# DoorNode.net
KiCad netlist of a schematic drawn in Altium Designer
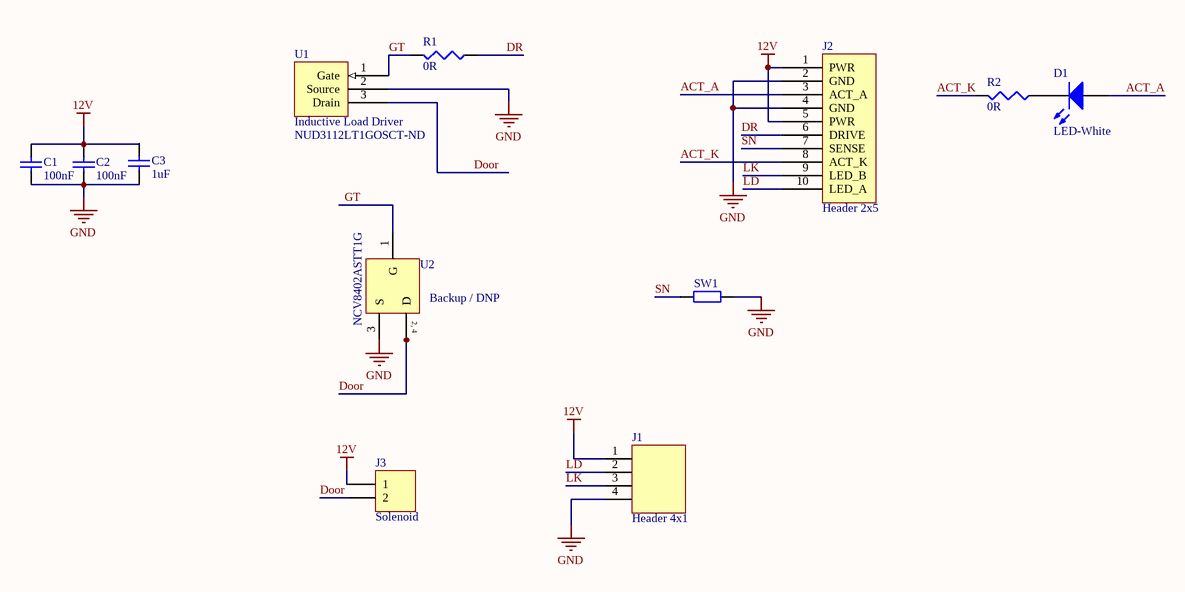
[diagram p0: DoorNode.SchDoc]

(export (version "E")
  (design (tool "Eeschema 10.0.6"))
  (components
    (comp (ref "C1")
      (value "100nF")
      (footprint "C1206")
      (description "Capacitor (Semiconductor SIM Model)")
      (fields (field (name "PUBLISHER") "Altium Limited"))
      (libsource (lib "ToolDoorController") (part "Cap 100nF"))
    )
    (comp (ref "C2")
      (value "100nF")
      (footprint "C1206")
      (description "Capacitor (Semiconductor SIM Model)")
      (fields (field (name "PUBLISHER") "Altium Limited"))
      (libsource (lib "ToolDoorController") (part "Cap 100nF"))
    )
    (comp (ref "C3")
      (value "1uF")
      (footprint "C1206")
      (description "Capacitor (Semiconductor SIM Model)")
      (fields (field (name "PUBLISHER") "Altium Limited"))
      (libsource (lib "ToolDoorController") (part "Cap 1uF"))
    )
    (comp (ref "D1")
      (value "LED-White")
      (footprint "STW8Q14")
      (description "White")
      (fields (field (name "PUBLISHER") "Altium Limited"))
      (libsource (lib "DoorNode") (part "LED-White"))
    )
    (comp (ref "J1")
      (value "Header 4x1")
      (footprint "4x1")
      (fields (field (name "PUBLISHER") "Altium Limited"))
      (libsource (lib "DoorNode") (part "Header 4x1"))
    )
    (comp (ref "J2")
      (value "Header 2x5")
      (footprint "2x5")
      (description "Header")
      (libsource (lib "DoorNode") (part "Header 2x5a"))
    )
    (comp (ref "J3")
      (value "Solenoid")
      (footprint "JST-XH")
      (description "Header, 2-Pin")
      (fields (field (name "PUBLISHER") "Altium Limited"))
      (libsource (lib "DoorNode") (part "Header 2 JST-XH"))
    )
    (comp (ref "R1")
      (value "0R")
      (footprint "C1206")
      (description "Resistor")
      (fields (field (name "PUBLISHER") "Altium Limited"))
      (libsource (lib "ToolDoorController") (part "Resistor-10K"))
    )
    (comp (ref "R2")
      (value "0R")
      (footprint "C1206")
      (description "Resistor")
      (fields (field (name "PUBLISHER") "Altium Limited"))
      (libsource (lib "ToolDoorController") (part "Resistor-10K"))
    )
    (comp (ref "SW1")
      (value "Switch")
      (footprint "ReedSwitch")
      (description "ReedSwitch")
      (fields (field (name "PUBLISHER") "Altium Limited"))
      (libsource (lib "DoorNode") (part "Switch"))
    )
    (comp (ref "U1")
      (value "Inductive Load Driver")
      (footprint "SOT-23")
      (description "Integrated Relay,  Inductive Load Driver")
      (fields (field (name "SUPPLIER PART NUMBER 1") "NUD3112LT1GOSCT-ND"))
      (libsource (lib "DoorNode") (part "NUD3112"))
    )
    (comp (ref "U2")
      (value "NCV8402ASTT1G")
      (footprint "ONSC-SOT-223-4-318E-04_V")
      (fields (field (name "MANUFACTURER") "On Semiconductor"))
      (libsource (lib "Altium Content Vault") (part "ONSC-ProNMOS-G1S3D24_B-4"))
    )
  )
  (nets
    (net (code "1") (name "/ACT_A") (class "Default")
      (node (ref "D1") (pin "2") (pinfunction "A_2") (pintype "passive"))
      (node (ref "J2") (pin "3") (pinfunction "ACT_A_3") (pintype "power_in"))
    )
    (net (code "2") (name "/ACT_K") (class "Default")
      (node (ref "J2") (pin "8") (pinfunction "ACT_K_8") (pintype "power_in"))
      (node (ref "R2") (pin "2") (pinfunction "2_2") (pintype "passive"))
    )
    (net (code "3") (name "/DR") (class "Default")
      (node (ref "J2") (pin "6") (pinfunction "DRIVE_6") (pintype "power_in"))
      (node (ref "R1") (pin "1") (pinfunction "1_1") (pintype "passive"))
    )
    (net (code "4") (name "/Door") (class "Default")
      (node (ref "J3") (pin "2") (pinfunction "2_2") (pintype "passive"))
      (node (ref "U1") (pin "3") (pinfunction "Drain_3") (pintype "power_in"))
      (node (ref "U2") (pin "2") (pinfunction "D_2") (pintype "passive"))
      (node (ref "U2") (pin "4") (pinfunction "D_4") (pintype "passive"))
    )
    (net (code "5") (name "/GT") (class "Default")
      (node (ref "R1") (pin "2") (pinfunction "2_2") (pintype "passive"))
      (node (ref "U1") (pin "1") (pinfunction "Gate_1") (pintype "input"))
      (node (ref "U2") (pin "1") (pinfunction "G_1") (pintype "passive"))
    )
    (net (code "6") (name "/LD") (class "Default")
      (node (ref "J1") (pin "2") (pintype "passive"))
      (node (ref "J2") (pin "10") (pinfunction "LED_A_10") (pintype "power_in"))
    )
    (net (code "7") (name "/LK") (class "Default")
      (node (ref "J1") (pin "3") (pintype "passive"))
      (node (ref "J2") (pin "9") (pinfunction "LED_B_9") (pintype "power_in"))
    )
    (net (code "8") (name "/SN") (class "Default")
      (node (ref "J2") (pin "7") (pinfunction "SENSE_7") (pintype "power_in"))
      (node (ref "SW1") (pin "2") (pinfunction "2_2") (pintype "passive"))
    )
    (net (code "9") (name "12V") (class "Default")
      (node (ref "C1") (pin "2") (pinfunction "2_2") (pintype "passive"))
      (node (ref "C2") (pin "2") (pinfunction "2_2") (pintype "passive"))
      (node (ref "C3") (pin "2") (pinfunction "2_2") (pintype "passive"))
      (node (ref "J1") (pin "1") (pintype "passive"))
      (node (ref "J2") (pin "1") (pinfunction "PWR_1") (pintype "power_in"))
      (node (ref "J2") (pin "5") (pinfunction "PWR_5") (pintype "power_in"))
      (node (ref "J3") (pin "1") (pinfunction "1_1") (pintype "passive"))
    )
    (net (code "10") (name "GND") (class "Default")
      (node (ref "C1") (pin "1") (pinfunction "1_1") (pintype "passive"))
      (node (ref "C2") (pin "1") (pinfunction "1_1") (pintype "passive"))
      (node (ref "C3") (pin "1") (pinfunction "1_1") (pintype "passive"))
      (node (ref "J1") (pin "4") (pintype "passive"))
      (node (ref "J2") (pin "2") (pinfunction "GND_2") (pintype "power_in"))
      (node (ref "J2") (pin "4") (pinfunction "GND_4") (pintype "power_in"))
      (node (ref "SW1") (pin "1") (pinfunction "1_1") (pintype "passive"))
      (node (ref "U1") (pin "2") (pinfunction "Source_2") (pintype "power_in"))
      (node (ref "U2") (pin "3") (pinfunction "S_3") (pintype "passive"))
    )
    (net (code "11") (name "Net-(D1-K)") (class "Default")
      (node (ref "D1") (pin "1") (pinfunction "K_1") (pintype "passive"))
      (node (ref "R2") (pin "1") (pinfunction "1_1") (pintype "passive"))
    )
  )
)
